# Multimode-VCF-LM13600_old.net
KiCad netlist of a schematic drawn in EAGLE
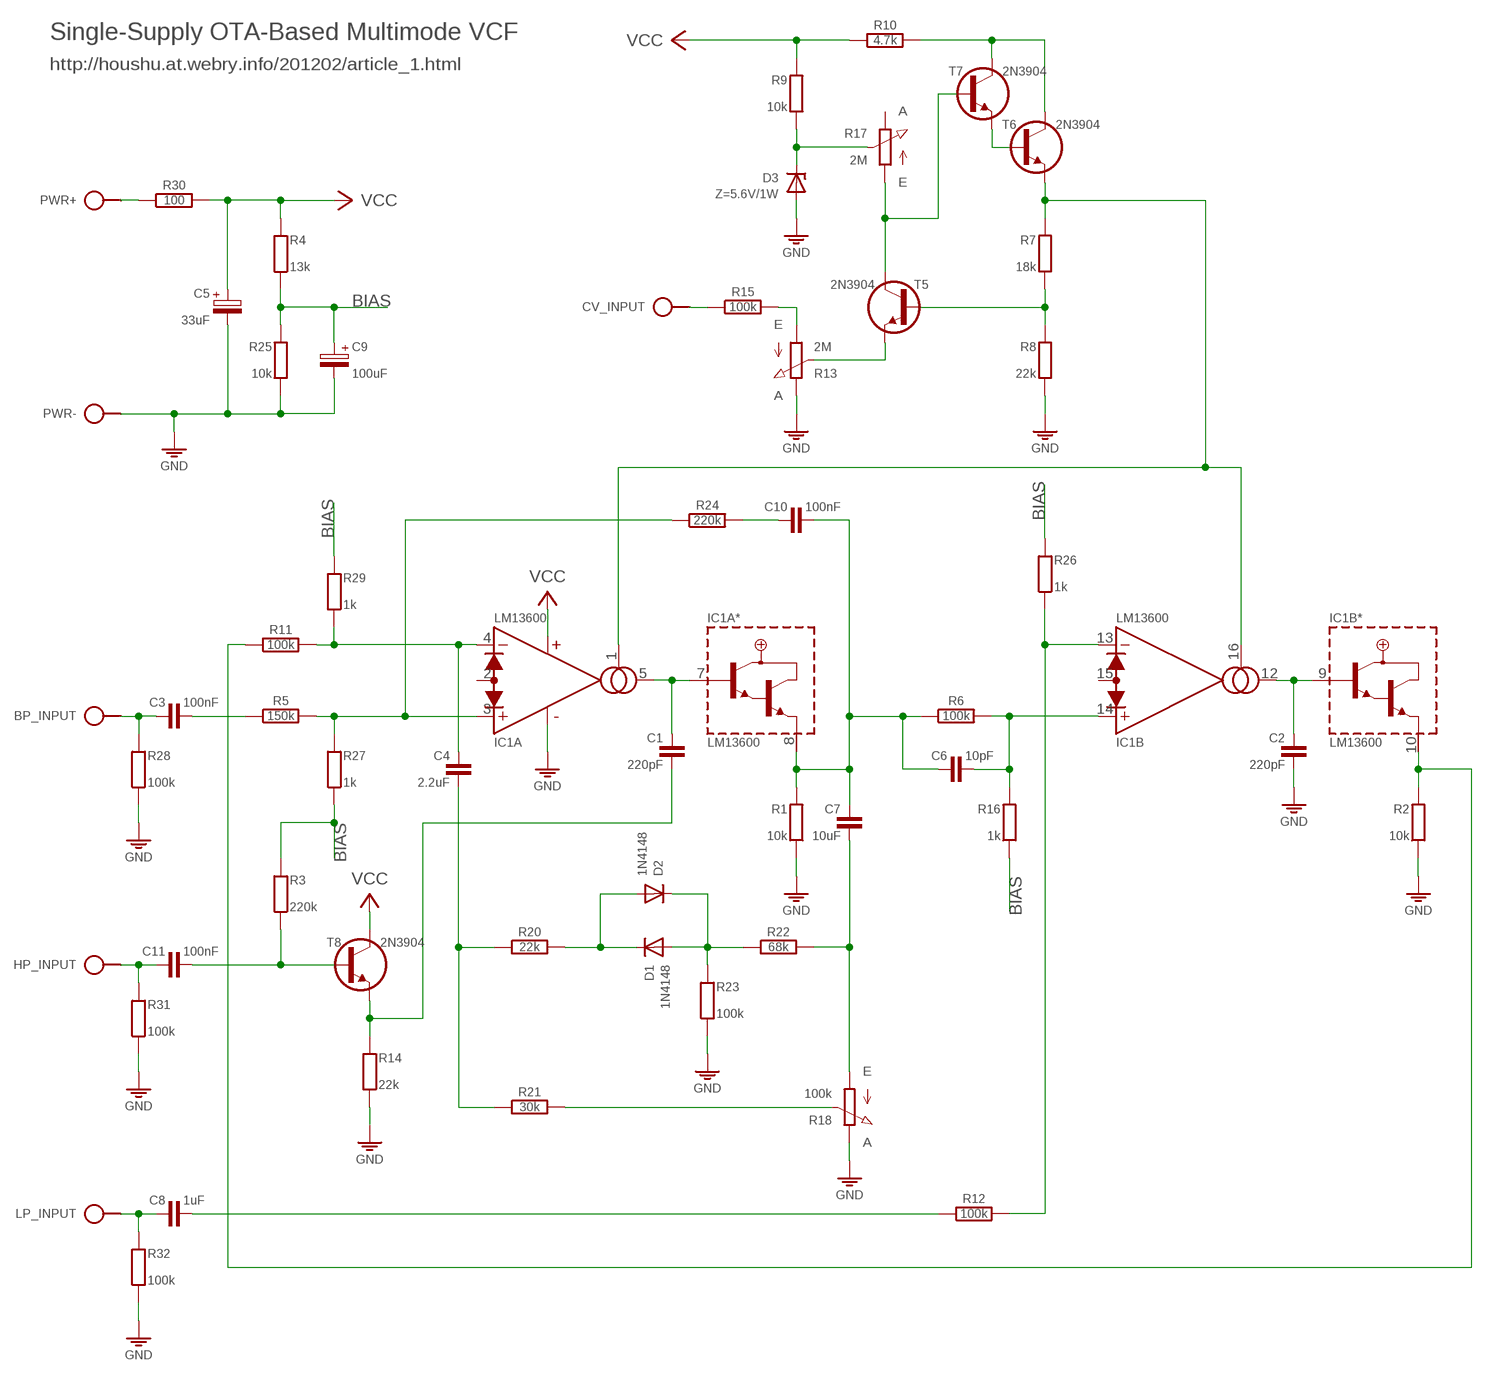
[diagram p0: schematic, sheet 1]

(export (version "E")
  (design (tool "Eeschema 10.0.6"))
  (components
    (comp (ref "BP_INPUT")
      (value "SPAD")
      (footprint "eagle-import:SPAD")
      (libsource (lib "eagle-import") (part "SPAD"))
    )
    (comp (ref "C1")
      (value "220pF")
      (footprint "eagle-import:C050-020X036_V")
      (libsource (lib "eagle-import") (part "C050-020X036/V"))
    )
    (comp (ref "C2")
      (value "220pF")
      (footprint "eagle-import:C050-020X036_V")
      (libsource (lib "eagle-import") (part "C050-020X036/V"))
    )
    (comp (ref "C3")
      (value "100nF")
      (footprint "eagle-import:C050-020X044")
      (libsource (lib "eagle-import") (part "C-H050-020X044"))
    )
    (comp (ref "C4")
      (value "2.2uF")
      (footprint "eagle-import:C050-024X044_V")
      (libsource (lib "eagle-import") (part "C050-024X044/V"))
    )
    (comp (ref "C5")
      (value "33uF")
      (footprint "eagle-import:E2.5-4_V")
      (libsource (lib "eagle-import") (part "CPOLE2,5-4/V"))
    )
    (comp (ref "C6")
      (value "10pF")
      (footprint "eagle-import:C050-020X036")
      (libsource (lib "eagle-import") (part "C-H050-020X036"))
    )
    (comp (ref "C7")
      (value "10uF")
      (footprint "eagle-import:C050-020X036_V")
      (libsource (lib "eagle-import") (part "C050-020X036/V"))
    )
    (comp (ref "C8")
      (value "1uF")
      (footprint "eagle-import:C050-024X044")
      (libsource (lib "eagle-import") (part "C-H050-024X044"))
    )
    (comp (ref "C9")
      (value "100uF")
      (footprint "eagle-import:E2.5-4_V")
      (libsource (lib "eagle-import") (part "CPOLE2,5-4/V"))
    )
    (comp (ref "C10")
      (value "100nF")
      (footprint "eagle-import:C050-020X044")
      (libsource (lib "eagle-import") (part "C-H050-020X044"))
    )
    (comp (ref "C11")
      (value "100nF")
      (footprint "eagle-import:C050-020X044_V")
      (libsource (lib "eagle-import") (part "C-H050-020X044/V"))
    )
    (comp (ref "CV_INPUT")
      (value "SPAD")
      (footprint "eagle-import:SPAD")
      (libsource (lib "eagle-import") (part "SPAD"))
    )
    (comp (ref "D1")
      (value "1N4148")
      (footprint "eagle-import:DO34-2,5-A")
      (libsource (lib "eagle-import") (part "1N414834-2,5-A"))
    )
    (comp (ref "D2")
      (value "1N4148")
      (footprint "eagle-import:DO34-2,5")
      (libsource (lib "eagle-import") (part "1N414834-2,5"))
    )
    (comp (ref "D3")
      (value "Z=5.6V/1W")
      (footprint "eagle-import:DO35Z7_V")
      (libsource (lib "eagle-import") (part "Z-DIODE-35Z7/V"))
    )
    (comp (ref "HP_INPUT")
      (value "SPAD")
      (footprint "eagle-import:SPAD")
      (libsource (lib "eagle-import") (part "SPAD"))
    )
    (comp (ref "IC1")
      (value "LM13600")
      (footprint "eagle-import:DIL16")
      (libsource (lib "eagle-import") (part "LM13600"))
    )
    (comp (ref "LP_INPUT")
      (value "SPAD")
      (footprint "eagle-import:SPAD")
      (libsource (lib "eagle-import") (part "SPAD"))
    )
    (comp (ref "PWR")
      (value "SPAD+--+")
      (footprint "eagle-import:SPAD-+")
      (libsource (lib "eagle-import") (part "SPAD+--+"))
    )
    (comp (ref "R1")
      (value "10k")
      (footprint "eagle-import:0204_10-V")
      (libsource (lib "eagle-import") (part "R0204/10-V"))
    )
    (comp (ref "R2")
      (value "10k")
      (footprint "eagle-import:0204_10")
      (libsource (lib "eagle-import") (part "R0204/10"))
    )
    (comp (ref "R3")
      (value "220k")
      (footprint "eagle-import:0204_10-V")
      (libsource (lib "eagle-import") (part "R0204/10-V"))
    )
    (comp (ref "R4")
      (value "13k")
      (footprint "eagle-import:0204_10-V")
      (libsource (lib "eagle-import") (part "R0204/10-V"))
    )
    (comp (ref "R5")
      (value "150k")
      (footprint "eagle-import:0204_10")
      (libsource (lib "eagle-import") (part "R-H0204/10"))
    )
    (comp (ref "R6")
      (value "100k")
      (footprint "eagle-import:0204_7-V")
      (libsource (lib "eagle-import") (part "R-H0204/7-V"))
    )
    (comp (ref "R7")
      (value "18k")
      (footprint "eagle-import:0204_10-V")
      (libsource (lib "eagle-import") (part "R0204/10-V"))
    )
    (comp (ref "R8")
      (value "22k")
      (footprint "eagle-import:0204_10-V")
      (libsource (lib "eagle-import") (part "R0204/10-V"))
    )
    (comp (ref "R9")
      (value "10k")
      (footprint "eagle-import:0204_10-V")
      (libsource (lib "eagle-import") (part "R0204/10-V"))
    )
    (comp (ref "R10")
      (value "4.7k")
      (footprint "eagle-import:0204_10")
      (libsource (lib "eagle-import") (part "R-H0204/10"))
    )
    (comp (ref "R11")
      (value "100k")
      (footprint "eagle-import:0204_10")
      (libsource (lib "eagle-import") (part "R-H0204/10"))
    )
    (comp (ref "R12")
      (value "100k")
      (footprint "eagle-import:0204_10")
      (libsource (lib "eagle-import") (part "R-H0204/10"))
    )
    (comp (ref "R13")
      (value "2M")
      (footprint "eagle-import:POT-V")
      (libsource (lib "eagle-import") (part "POT-V"))
    )
    (comp (ref "R14")
      (value "22k")
      (footprint "eagle-import:0204_10-V")
      (libsource (lib "eagle-import") (part "R0204/10-V"))
    )
    (comp (ref "R15")
      (value "100k")
      (footprint "eagle-import:0204_10")
      (libsource (lib "eagle-import") (part "R-H0204/10"))
    )
    (comp (ref "R16")
      (value "1k")
      (footprint "eagle-import:0204_7-V")
      (libsource (lib "eagle-import") (part "R0204/7-V"))
    )
    (comp (ref "R17")
      (value "2M")
      (footprint "eagle-import:POT-V")
      (libsource (lib "eagle-import") (part "POT-V"))
    )
    (comp (ref "R18")
      (value "100k")
      (footprint "eagle-import:POT")
      (libsource (lib "eagle-import") (part "POT"))
    )
    (comp (ref "R20")
      (value "22k")
      (footprint "eagle-import:0204_10")
      (libsource (lib "eagle-import") (part "R-H0204/10"))
    )
    (comp (ref "R21")
      (value "30k")
      (footprint "eagle-import:0204_10")
      (libsource (lib "eagle-import") (part "R-H0204/10"))
    )
    (comp (ref "R22")
      (value "68k")
      (footprint "eagle-import:0204_10")
      (libsource (lib "eagle-import") (part "R-H0204/10"))
    )
    (comp (ref "R23")
      (value "100k")
      (footprint "eagle-import:0204_10-V")
      (libsource (lib "eagle-import") (part "R0204/10-V"))
    )
    (comp (ref "R24")
      (value "220k")
      (footprint "eagle-import:0204_10-V")
      (libsource (lib "eagle-import") (part "R-H0204/10-V"))
    )
    (comp (ref "R25")
      (value "10k")
      (footprint "eagle-import:0204_10-V")
      (libsource (lib "eagle-import") (part "R0204/10-V"))
    )
    (comp (ref "R26")
      (value "1k")
      (footprint "eagle-import:0204_7")
      (libsource (lib "eagle-import") (part "R0204/7"))
    )
    (comp (ref "R27")
      (value "1k")
      (footprint "eagle-import:0204_10-V")
      (libsource (lib "eagle-import") (part "R0204/10-V"))
    )
    (comp (ref "R28")
      (value "100k")
      (footprint "eagle-import:0204_10-V")
      (libsource (lib "eagle-import") (part "R0204/10-V"))
    )
    (comp (ref "R29")
      (value "1k")
      (footprint "eagle-import:0204_10-V")
      (libsource (lib "eagle-import") (part "R0204/10-V"))
    )
    (comp (ref "R30")
      (value "100")
      (footprint "eagle-import:0204_10")
      (libsource (lib "eagle-import") (part "R-H0204/10"))
    )
    (comp (ref "R31")
      (value "100k")
      (footprint "eagle-import:0204_10-V")
      (libsource (lib "eagle-import") (part "R0204/10-V"))
    )
    (comp (ref "R32")
      (value "100k")
      (footprint "eagle-import:0204_10-V")
      (libsource (lib "eagle-import") (part "R0204/10-V"))
    )
    (comp (ref "T5")
      (value "2N3904")
      (footprint "eagle-import:TO92")
      (libsource (lib "eagle-import") (part "2N3904"))
    )
    (comp (ref "T6")
      (value "2N3904")
      (footprint "eagle-import:TO92")
      (libsource (lib "eagle-import") (part "2N3904"))
    )
    (comp (ref "T7")
      (value "2N3904")
      (footprint "eagle-import:TO92")
      (libsource (lib "eagle-import") (part "2N3904"))
    )
    (comp (ref "T8")
      (value "2N3904")
      (footprint "eagle-import:TO92")
      (libsource (lib "eagle-import") (part "2N3904"))
    )
  )
  (nets
    (net (code "1") (name "/BIAS") (class "Default")
      (node (ref "C9") (pin "+") (pinfunction "+_+") (pintype "passive"))
      (node (ref "R16") (pin "1") (pinfunction "2_1") (pintype "passive"))
      (node (ref "R25") (pin "1") (pinfunction "1_1") (pintype "passive"))
      (node (ref "R26") (pin "2") (pinfunction "1_2") (pintype "passive"))
      (node (ref "R27") (pin "2") (pinfunction "2_2") (pintype "passive"))
      (node (ref "R29") (pin "1") (pinfunction "1_1") (pintype "passive"))
      (node (ref "R3") (pin "1") (pinfunction "1_1") (pintype "passive"))
      (node (ref "R4") (pin "2") (pinfunction "2_2") (pintype "passive"))
    )
    (net (code "2") (name "GND") (class "Default")
      (node (ref "C2") (pin "2") (pinfunction "2_2") (pintype "passive"))
      (node (ref "C5") (pin "-") (pinfunction "-_-") (pintype "passive"))
      (node (ref "C9") (pin "-") (pinfunction "-_-") (pintype "passive"))
      (node (ref "D3") (pin "A") (pinfunction "A_A") (pintype "passive"))
      (node (ref "IC1") (pin "6") (pinfunction "V-_6") (pintype "power_in"))
      (node (ref "PWR") (pin "1") (pinfunction "P$1_1") (pintype "passive"))
      (node (ref "R1") (pin "2") (pinfunction "2_2") (pintype "passive"))
      (node (ref "R13") (pin "E") (pinfunction "E_E") (pintype "passive"))
      (node (ref "R14") (pin "2") (pinfunction "2_2") (pintype "passive"))
      (node (ref "R18") (pin "3") (pinfunction "E_3") (pintype "passive"))
      (node (ref "R2") (pin "1") (pinfunction "2_1") (pintype "passive"))
      (node (ref "R23") (pin "2") (pinfunction "2_2") (pintype "passive"))
      (node (ref "R25") (pin "2") (pinfunction "2_2") (pintype "passive"))
      (node (ref "R28") (pin "2") (pinfunction "2_2") (pintype "passive"))
      (node (ref "R31") (pin "2") (pinfunction "2_2") (pintype "passive"))
      (node (ref "R32") (pin "2") (pinfunction "2_2") (pintype "passive"))
      (node (ref "R8") (pin "2") (pinfunction "2_2") (pintype "passive"))
    )
    (net (code "3") (name "Net-(BP_INPUT-P$1)") (class "Default")
      (node (ref "BP_INPUT") (pin "1") (pinfunction "P$1_1") (pintype "passive"))
      (node (ref "C3") (pin "1") (pinfunction "1_1") (pintype "passive"))
      (node (ref "R28") (pin "1") (pinfunction "1_1") (pintype "passive"))
    )
    (net (code "4") (name "Net-(C3-Pad2)") (class "Default")
      (node (ref "C3") (pin "2") (pinfunction "2_2") (pintype "passive"))
      (node (ref "R5") (pin "1") (pinfunction "1_1") (pintype "passive"))
    )
    (net (code "5") (name "Net-(C4-Pad2)") (class "Default")
      (node (ref "C4") (pin "2") (pinfunction "2_2") (pintype "passive"))
      (node (ref "R20") (pin "1") (pinfunction "1_1") (pintype "passive"))
      (node (ref "R21") (pin "1") (pinfunction "1_1") (pintype "passive"))
    )
    (net (code "6") (name "Net-(C8-Pad2)") (class "Default")
      (node (ref "C8") (pin "2") (pinfunction "2_2") (pintype "passive"))
      (node (ref "R12") (pin "1") (pinfunction "1_1") (pintype "passive"))
    )
    (net (code "7") (name "Net-(C10-Pad1)") (class "Default")
      (node (ref "C10") (pin "1") (pinfunction "1_1") (pintype "passive"))
      (node (ref "R24") (pin "2") (pinfunction "2_2") (pintype "passive"))
    )
    (net (code "8") (name "Net-(CV_INPUT-P$1)") (class "Default")
      (node (ref "CV_INPUT") (pin "1") (pinfunction "P$1_1") (pintype "passive"))
      (node (ref "R15") (pin "1") (pinfunction "1_1") (pintype "passive"))
    )
    (net (code "9") (name "Net-(D1-PadA)") (class "Default")
      (node (ref "D1") (pin "A") (pinfunction "A_A") (pintype "passive"))
      (node (ref "D2") (pin "C") (pinfunction "C_C") (pintype "passive"))
      (node (ref "R22") (pin "1") (pinfunction "1_1") (pintype "passive"))
      (node (ref "R23") (pin "1") (pinfunction "1_1") (pintype "passive"))
    )
    (net (code "10") (name "Net-(D1-PadC)") (class "Default")
      (node (ref "D1") (pin "C") (pinfunction "C_C") (pintype "passive"))
      (node (ref "D2") (pin "A") (pinfunction "A_A") (pintype "passive"))
      (node (ref "R20") (pin "2") (pinfunction "2_2") (pintype "passive"))
    )
    (net (code "11") (name "Net-(D3-PadC)") (class "Default")
      (node (ref "D3") (pin "C") (pinfunction "C_C") (pintype "passive"))
      (node (ref "R17") (pin "S") (pinfunction "S_S") (pintype "passive"))
      (node (ref "R9") (pin "2") (pinfunction "2_2") (pintype "passive"))
    )
    (net (code "12") (name "Net-(HP_INPUT-P$1)") (class "Default")
      (node (ref "C11") (pin "1") (pinfunction "1_1") (pintype "passive"))
      (node (ref "HP_INPUT") (pin "1") (pinfunction "P$1_1") (pintype "passive"))
      (node (ref "R31") (pin "1") (pinfunction "1_1") (pintype "passive"))
    )
    (net (code "13") (name "Net-(IC1A-+IN)") (class "Default")
      (node (ref "IC1") (pin "3") (pinfunction "+IN_3") (pintype "input"))
      (node (ref "R24") (pin "1") (pinfunction "1_1") (pintype "passive"))
      (node (ref "R27") (pin "1") (pinfunction "1_1") (pintype "passive"))
      (node (ref "R5") (pin "2") (pinfunction "2_2") (pintype "passive"))
    )
    (net (code "14") (name "Net-(IC1A--IN)") (class "Default")
      (node (ref "C4") (pin "1") (pinfunction "1_1") (pintype "passive"))
      (node (ref "IC1") (pin "4") (pinfunction "-IN_4") (pintype "input"))
      (node (ref "R11") (pin "2") (pinfunction "2_2") (pintype "passive"))
      (node (ref "R29") (pin "2") (pinfunction "2_2") (pintype "passive"))
    )
    (net (code "15") (name "Net-(IC1A-AMP{slash}BIAS)") (class "Default")
      (node (ref "IC1") (pin "1") (pinfunction "AMP/BIAS_1") (pintype "input"))
      (node (ref "IC1") (pin "16") (pinfunction "AMP/BIAS_16") (pintype "input"))
      (node (ref "R7") (pin "1") (pinfunction "1_1") (pintype "passive"))
      (node (ref "T6") (pin "1") (pinfunction "E_1") (pintype "passive"))
    )
    (net (code "16") (name "Net-(IC1A-OUT)") (class "Default")
      (node (ref "C1") (pin "1") (pinfunction "1_1") (pintype "passive"))
      (node (ref "IC1") (pin "5") (pinfunction "OUT_5") (pintype "output"))
      (node (ref "IC1") (pin "7") (pinfunction "BUFF/IN_7") (pintype "input"))
    )
    (net (code "17") (name "Net-(IC1B-BUFF{slash}OUT)") (class "Default")
      (node (ref "C10") (pin "2") (pinfunction "2_2") (pintype "passive"))
      (node (ref "C6") (pin "1") (pinfunction "1_1") (pintype "passive"))
      (node (ref "C7") (pin "1") (pinfunction "1_1") (pintype "passive"))
      (node (ref "IC1") (pin "8") (pinfunction "BUFF/OUT_8") (pintype "output"))
      (node (ref "R1") (pin "1") (pinfunction "1_1") (pintype "passive"))
      (node (ref "R6") (pin "1") (pinfunction "1_1") (pintype "passive"))
    )
    (net (code "18") (name "Net-(IC1C-+IN)") (class "Default")
      (node (ref "C6") (pin "2") (pinfunction "2_2") (pintype "passive"))
      (node (ref "IC1") (pin "14") (pinfunction "+IN_14") (pintype "input"))
      (node (ref "R16") (pin "2") (pinfunction "1_2") (pintype "passive"))
      (node (ref "R6") (pin "2") (pinfunction "2_2") (pintype "passive"))
    )
    (net (code "19") (name "Net-(IC1C--IN)") (class "Default")
      (node (ref "IC1") (pin "13") (pinfunction "-IN_13") (pintype "input"))
      (node (ref "R12") (pin "2") (pinfunction "2_2") (pintype "passive"))
      (node (ref "R26") (pin "1") (pinfunction "2_1") (pintype "passive"))
    )
    (net (code "20") (name "Net-(IC1C-OUT)") (class "Default")
      (node (ref "C2") (pin "1") (pinfunction "1_1") (pintype "passive"))
      (node (ref "IC1") (pin "12") (pinfunction "OUT_12") (pintype "output"))
      (node (ref "IC1") (pin "9") (pinfunction "BUFF/IN_9") (pintype "input"))
    )
    (net (code "21") (name "Net-(IC1D-BUFF{slash}OUT)") (class "Default")
      (node (ref "IC1") (pin "10") (pinfunction "BUFF/OUT_10") (pintype "output"))
      (node (ref "R11") (pin "1") (pinfunction "1_1") (pintype "passive"))
      (node (ref "R2") (pin "2") (pinfunction "1_2") (pintype "passive"))
    )
    (net (code "22") (name "Net-(LP_INPUT-P$1)") (class "Default")
      (node (ref "C8") (pin "1") (pinfunction "1_1") (pintype "passive"))
      (node (ref "LP_INPUT") (pin "1") (pinfunction "P$1_1") (pintype "passive"))
      (node (ref "R32") (pin "1") (pinfunction "1_1") (pintype "passive"))
    )
    (net (code "23") (name "Net-(PWRA-P$1)") (class "Default")
      (node (ref "PWR") (pin "2") (pinfunction "P$1_2") (pintype "passive"))
      (node (ref "R30") (pin "1") (pinfunction "1_1") (pintype "passive"))
    )
    (net (code "24") (name "Net-(R13-PadA)") (class "Default")
      (node (ref "R13") (pin "A") (pinfunction "A_A") (pintype "passive"))
      (node (ref "R15") (pin "2") (pinfunction "2_2") (pintype "passive"))
    )
    (net (code "25") (name "Net-(R18-A)") (class "Default")
      (node (ref "C7") (pin "2") (pinfunction "2_2") (pintype "passive"))
      (node (ref "R18") (pin "1") (pinfunction "A_1") (pintype "passive"))
      (node (ref "R22") (pin "2") (pinfunction "2_2") (pintype "passive"))
    )
    (net (code "26") (name "Net-(R18-S)") (class "Default")
      (node (ref "R18") (pin "2") (pinfunction "S_2") (pintype "passive"))
      (node (ref "R21") (pin "2") (pinfunction "2_2") (pintype "passive"))
    )
    (net (code "27") (name "Net-(T5-B)") (class "Default")
      (node (ref "R7") (pin "2") (pinfunction "2_2") (pintype "passive"))
      (node (ref "R8") (pin "1") (pinfunction "1_1") (pintype "passive"))
      (node (ref "T5") (pin "2") (pinfunction "B_2") (pintype "passive"))
    )
    (net (code "28") (name "Net-(T5-C)") (class "Default")
      (node (ref "R17") (pin "A") (pinfunction "A_A") (pintype "passive"))
      (node (ref "T5") (pin "3") (pinfunction "C_3") (pintype "passive"))
      (node (ref "T7") (pin "2") (pinfunction "B_2") (pintype "passive"))
    )
    (net (code "29") (name "Net-(T5-E)") (class "Default")
      (node (ref "R13") (pin "S") (pinfunction "S_S") (pintype "passive"))
      (node (ref "T5") (pin "1") (pinfunction "E_1") (pintype "passive"))
    )
    (net (code "30") (name "Net-(T6-B)") (class "Default")
      (node (ref "T6") (pin "2") (pinfunction "B_2") (pintype "passive"))
      (node (ref "T7") (pin "1") (pinfunction "E_1") (pintype "passive"))
    )
    (net (code "31") (name "Net-(T6-C)") (class "Default")
      (node (ref "R10") (pin "2") (pinfunction "2_2") (pintype "passive"))
      (node (ref "T6") (pin "3") (pinfunction "C_3") (pintype "passive"))
      (node (ref "T7") (pin "3") (pinfunction "C_3") (pintype "passive"))
    )
    (net (code "32") (name "Net-(T8-B)") (class "Default")
      (node (ref "C11") (pin "2") (pinfunction "2_2") (pintype "passive"))
      (node (ref "R3") (pin "2") (pinfunction "2_2") (pintype "passive"))
      (node (ref "T8") (pin "2") (pinfunction "B_2") (pintype "passive"))
    )
    (net (code "33") (name "Net-(T8-E)") (class "Default")
      (node (ref "C1") (pin "2") (pinfunction "2_2") (pintype "passive"))
      (node (ref "R14") (pin "1") (pinfunction "1_1") (pintype "passive"))
      (node (ref "T8") (pin "1") (pinfunction "E_1") (pintype "passive"))
    )
    (net (code "34") (name "VCC") (class "Default")
      (node (ref "C5") (pin "+") (pinfunction "+_+") (pintype "passive"))
      (node (ref "IC1") (pin "11") (pinfunction "V+_11") (pintype "power_in"))
      (node (ref "R10") (pin "1") (pinfunction "1_1") (pintype "passive"))
      (node (ref "R30") (pin "2") (pinfunction "2_2") (pintype "passive"))
      (node (ref "R4") (pin "1") (pinfunction "1_1") (pintype "passive"))
      (node (ref "R9") (pin "1") (pinfunction "1_1") (pintype "passive"))
      (node (ref "T8") (pin "3") (pinfunction "C_3") (pintype "passive"))
    )
    (net (code "35") (name "unconnected-(IC1A-DIODE{slash}BIAS-Pad2)") (class "Default")
      (node (ref "IC1") (pin "2") (pinfunction "DIODE/BIAS_2") (pintype "input"))
    )
    (net (code "36") (name "unconnected-(IC1C-DIODE{slash}BIAS-Pad15)") (class "Default")
      (node (ref "IC1") (pin "15") (pinfunction "DIODE/BIAS_15") (pintype "input"))
    )
    (net (code "37") (name "unconnected-(R17-PadE)") (class "Default")
      (node (ref "R17") (pin "E") (pinfunction "E_E") (pintype "passive"))
    )
  )
)
